# DisplayAddOn_V03-002.net
KiCad netlist of a schematic drawn in EAGLE
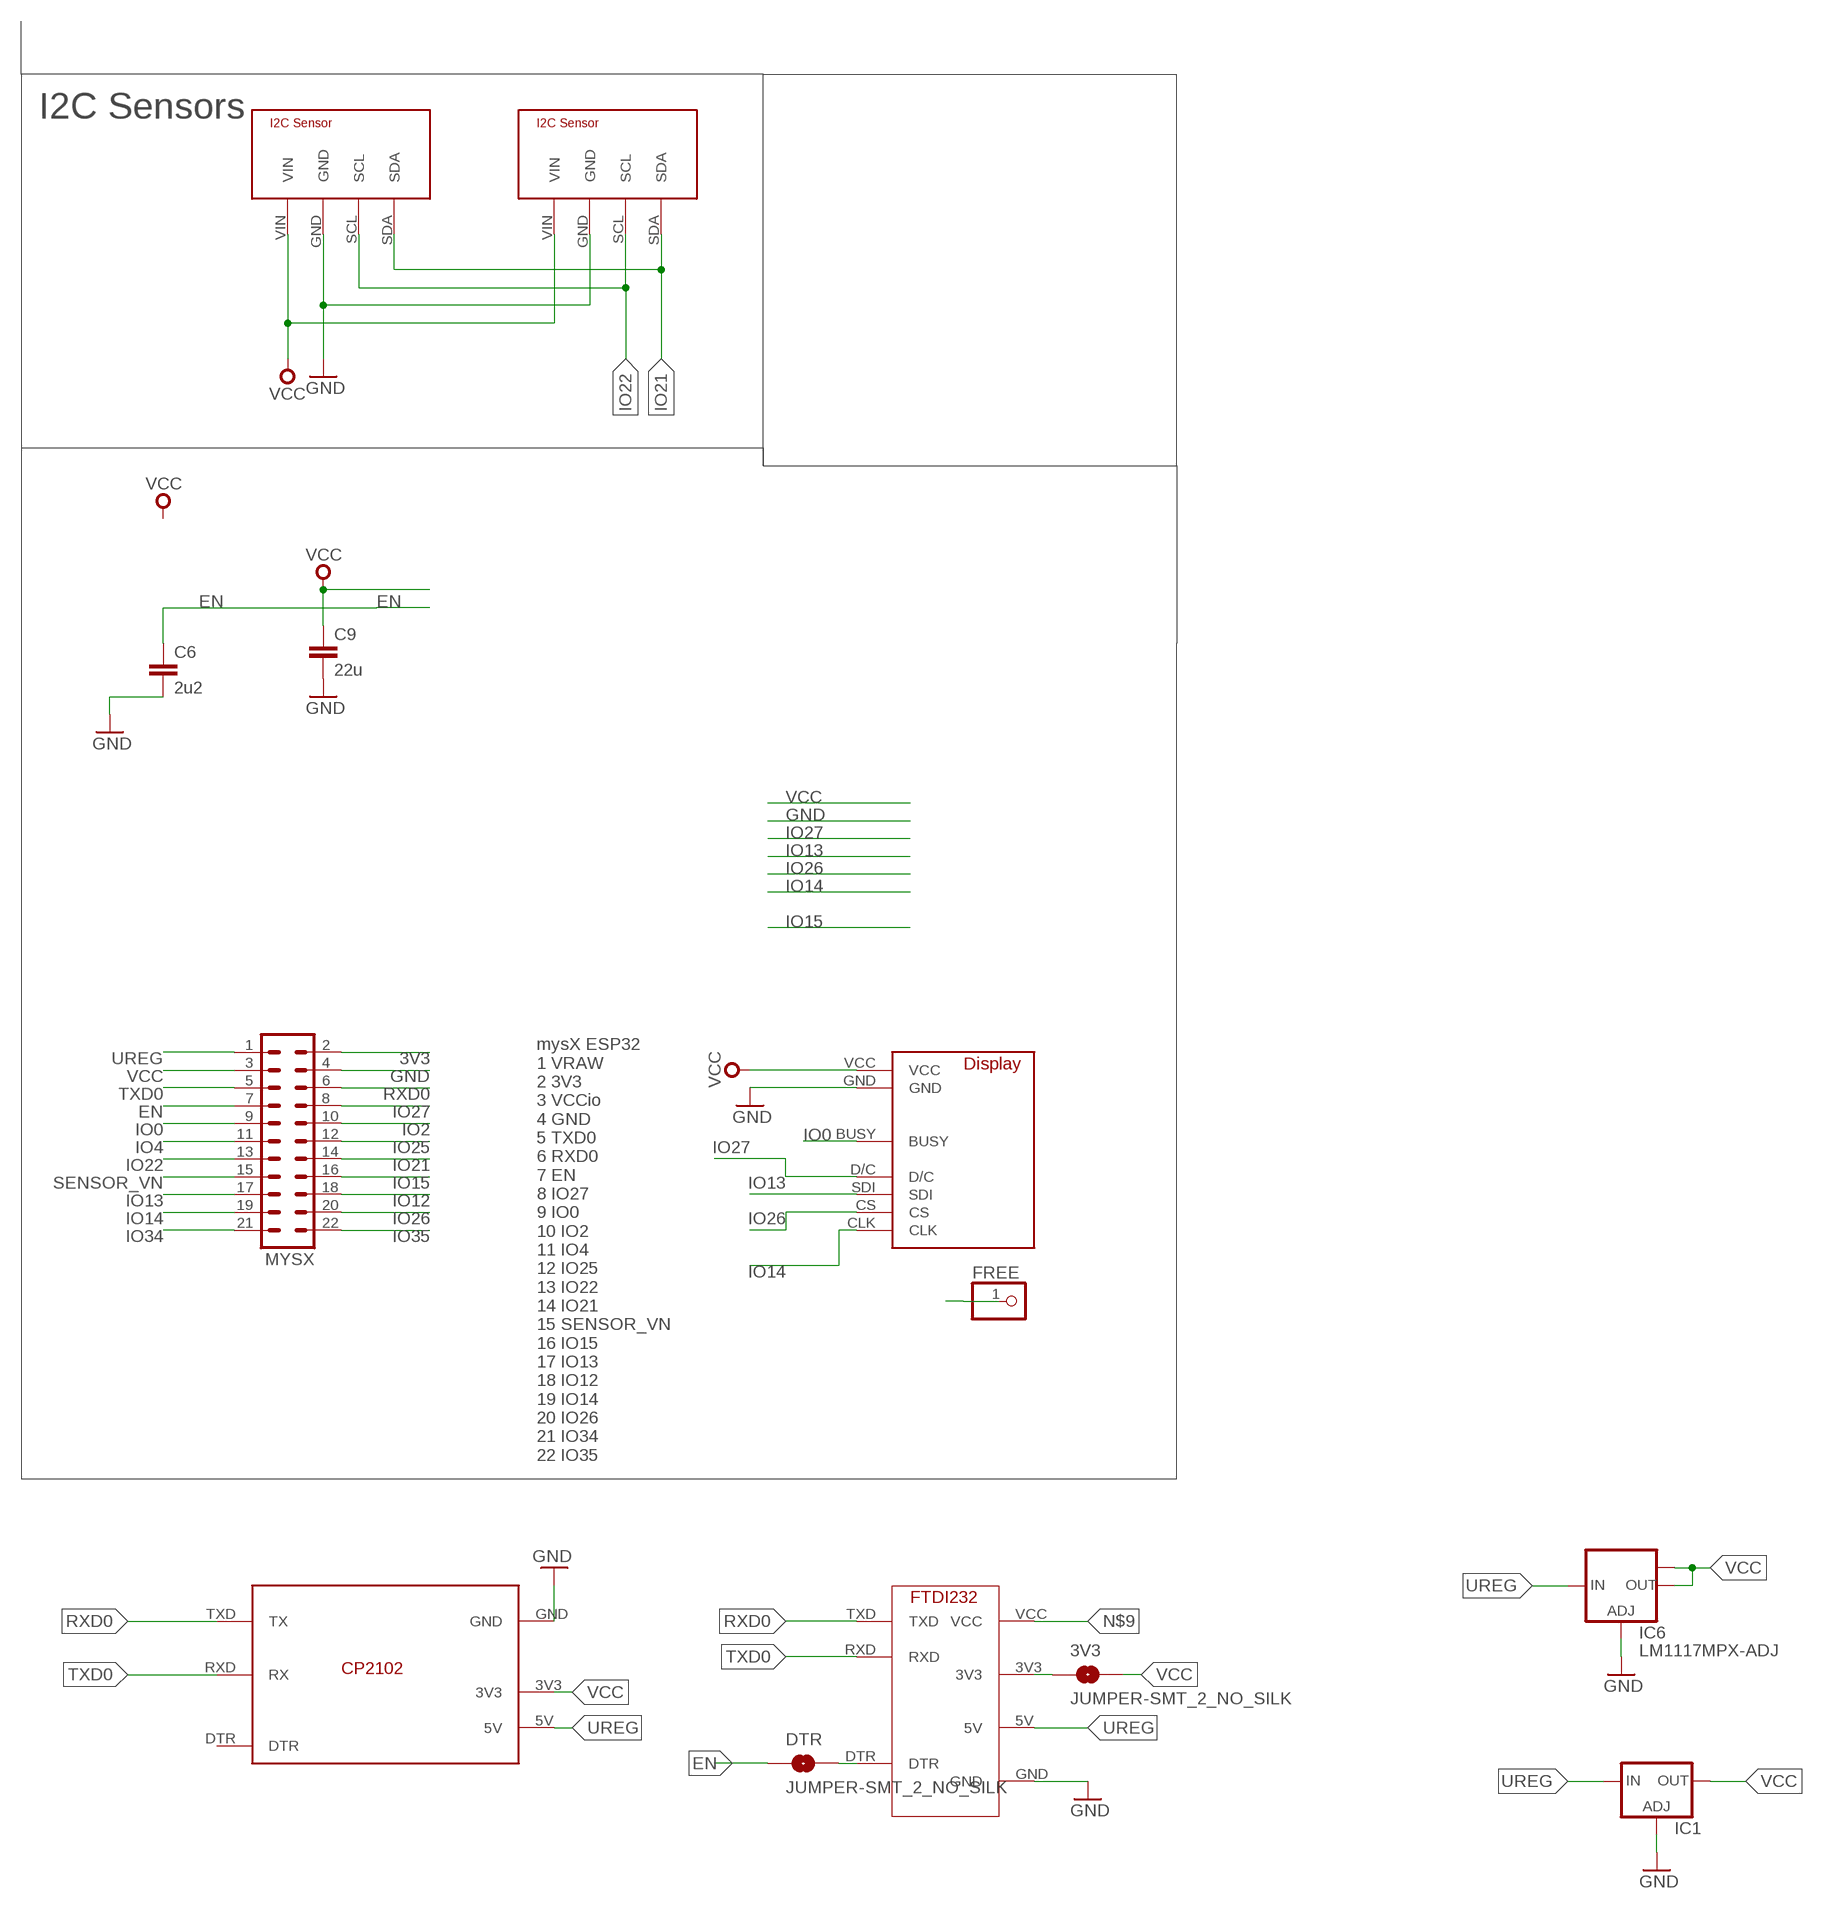
[diagram p0: schematic, sheet 1]

(export (version "E")
  (design (tool "Eeschema 10.0.6"))
  (components
    (comp (ref "3V3")
      (value "JUMPER-SMT_2_NO_SILK")
      (footprint "eagle-import:SMT-JUMPER_2_NO_SILK")
      (libsource (lib "eagle-import") (part "JUMPER-SMT_2_NO_SILK"))
    )
    (comp (ref "C6")
      (value "2u2")
      (footprint "eagle-import:C0805")
      (libsource (lib "eagle-import") (part "C-EUC0805"))
    )
    (comp (ref "C9")
      (value "22u")
      (footprint "eagle-import:C0805")
      (libsource (lib "eagle-import") (part "C-EUC0805"))
    )
    (comp (ref "DTR")
      (value "JUMPER-SMT_2_NO_SILK")
      (footprint "eagle-import:SMT-JUMPER_2_NO_SILK")
      (libsource (lib "eagle-import") (part "JUMPER-SMT_2_NO_SILK"))
    )
    (comp (ref "FREE")
      (value "PINHD-1X1")
      (footprint "eagle-import:1X01")
      (libsource (lib "eagle-import") (part "PINHD-1X1"))
    )
    (comp (ref "HELTEK")
      (value "ZUCZUG_1.54")
      (footprint "eagle-import:ZUCZUG_1.54INCH")
      (libsource (lib "eagle-import") (part "ZUCZUG_1.54"))
    )
    (comp (ref "IC1")
      (value "LD117ADT50TR")
      (footprint "eagle-import:DPACK")
      (libsource (lib "eagle-import") (part "LD117A?DT50TR"))
    )
    (comp (ref "IC6")
      (value "LM1117MPX-ADJ")
      (footprint "eagle-import:SOT223")
      (libsource (lib "eagle-import") (part "LM1117MPX-ADJ"))
    )
    (comp (ref "MYSX")
      (value "MA11-2")
      (footprint "eagle-import:MA11-2")
      (libsource (lib "eagle-import") (part "MA11-2"))
    )
    (comp (ref "U$1")
      (value "CP2101")
      (footprint "eagle-import:CP2101-BEAKOUT")
      (libsource (lib "eagle-import") (part "CP2101"))
    )
    (comp (ref "U$2")
      (value "I2C-BREAKOUT")
      (footprint "eagle-import:I2C_BREAKOUT")
      (libsource (lib "eagle-import") (part "I2C-BREAKOUT"))
    )
    (comp (ref "U$3")
      (value "FTDI232")
      (footprint "eagle-import:FTDI232-LARGE-LESS-PINS")
      (libsource (lib "eagle-import") (part "FTDI232"))
    )
    (comp (ref "U$4")
      (value "I2C-BREAKOUT")
      (footprint "eagle-import:I2C_BREAKOUT")
      (libsource (lib "eagle-import") (part "I2C-BREAKOUT"))
    )
  )
  (nets
    (net (code "1") (name "/3V3") (class "Default")
      (node (ref "MYSX") (pin "2") (pinfunction "2_2") (pintype "passive"))
    )
    (net (code "2") (name "/IO0") (class "Default")
      (node (ref "HELTEK") (pin "BUSY") (pinfunction "BUSY_BUSY") (pintype "bidirectional"))
      (node (ref "MYSX") (pin "9") (pinfunction "9_9") (pintype "passive"))
    )
    (net (code "3") (name "/IO2") (class "Default")
      (node (ref "MYSX") (pin "10") (pinfunction "10_10") (pintype "passive"))
    )
    (net (code "4") (name "/IO4") (class "Default")
      (node (ref "MYSX") (pin "11") (pinfunction "11_11") (pintype "passive"))
    )
    (net (code "5") (name "/IO12") (class "Default")
      (node (ref "MYSX") (pin "18") (pinfunction "18_18") (pintype "passive"))
    )
    (net (code "6") (name "/IO13") (class "Default")
      (node (ref "HELTEK") (pin "SDI") (pinfunction "SDI_SDI") (pintype "bidirectional"))
      (node (ref "MYSX") (pin "17") (pinfunction "17_17") (pintype "passive"))
    )
    (net (code "7") (name "/IO14") (class "Default")
      (node (ref "HELTEK") (pin "CLK") (pinfunction "CLK_CLK") (pintype "bidirectional"))
      (node (ref "MYSX") (pin "19") (pinfunction "19_19") (pintype "passive"))
    )
    (net (code "8") (name "/IO15") (class "Default")
      (node (ref "MYSX") (pin "16") (pinfunction "16_16") (pintype "passive"))
    )
    (net (code "9") (name "/IO25") (class "Default")
      (node (ref "MYSX") (pin "12") (pinfunction "12_12") (pintype "passive"))
    )
    (net (code "10") (name "/IO26") (class "Default")
      (node (ref "HELTEK") (pin "CS") (pinfunction "CS_CS") (pintype "bidirectional"))
      (node (ref "MYSX") (pin "20") (pinfunction "20_20") (pintype "passive"))
    )
    (net (code "11") (name "/IO27") (class "Default")
      (node (ref "HELTEK") (pin "D/C") (pinfunction "D/C_D/C") (pintype "bidirectional"))
      (node (ref "MYSX") (pin "8") (pinfunction "8_8") (pintype "passive"))
    )
    (net (code "12") (name "/IO34") (class "Default")
      (node (ref "MYSX") (pin "21") (pinfunction "21_21") (pintype "passive"))
    )
    (net (code "13") (name "/IO35") (class "Default")
      (node (ref "MYSX") (pin "22") (pinfunction "22_22") (pintype "passive"))
    )
    (net (code "14") (name "/SENSOR_VN") (class "Default")
      (node (ref "MYSX") (pin "15") (pinfunction "15_15") (pintype "passive"))
    )
    (net (code "15") (name "EN") (class "Default")
      (node (ref "C6") (pin "1") (pinfunction "1_1") (pintype "passive"))
      (node (ref "DTR") (pin "1") (pinfunction "1_1") (pintype "passive"))
      (node (ref "MYSX") (pin "7") (pinfunction "7_7") (pintype "passive"))
    )
    (net (code "16") (name "GND") (class "Default")
      (node (ref "C6") (pin "2") (pinfunction "2_2") (pintype "passive"))
      (node (ref "C9") (pin "2") (pinfunction "2_2") (pintype "passive"))
      (node (ref "HELTEK") (pin "GND") (pinfunction "GND_GND") (pintype "power_in"))
      (node (ref "IC1") (pin "1") (pinfunction "ADJ_1") (pintype "input"))
      (node (ref "IC6") (pin "1") (pinfunction "ADJ_1") (pintype "input"))
      (node (ref "MYSX") (pin "4") (pinfunction "4_4") (pintype "passive"))
      (node (ref "U$1") (pin "GND") (pinfunction "GND_GND") (pintype "power_in"))
      (node (ref "U$2") (pin "GND") (pinfunction "GND_GND") (pintype "bidirectional"))
      (node (ref "U$3") (pin "GND") (pinfunction "GND_GND") (pintype "bidirectional"))
      (node (ref "U$4") (pin "GND") (pinfunction "GND_GND") (pintype "bidirectional"))
    )
    (net (code "17") (name "IO21") (class "Default")
      (node (ref "MYSX") (pin "14") (pinfunction "14_14") (pintype "passive"))
      (node (ref "U$2") (pin "SDA") (pinfunction "SDA_SDA") (pintype "bidirectional"))
      (node (ref "U$4") (pin "SDA") (pinfunction "SDA_SDA") (pintype "bidirectional"))
    )
    (net (code "18") (name "IO22") (class "Default")
      (node (ref "MYSX") (pin "13") (pinfunction "13_13") (pintype "passive"))
      (node (ref "U$2") (pin "SCL") (pinfunction "SCL_SCL") (pintype "bidirectional"))
      (node (ref "U$4") (pin "SCL") (pinfunction "SCL_SCL") (pintype "bidirectional"))
    )
    (net (code "19") (name "N$9") (class "Default")
      (node (ref "U$3") (pin "VCC") (pinfunction "VCC_VCC") (pintype "bidirectional"))
    )
    (net (code "20") (name "Net-(3V3-Pad1)") (class "Default")
      (node (ref "3V3") (pin "1") (pinfunction "1_1") (pintype "passive"))
      (node (ref "U$3") (pin "3V3") (pinfunction "3V3_3V3") (pintype "bidirectional"))
    )
    (net (code "21") (name "Net-(DTR-Pad2)") (class "Default")
      (node (ref "DTR") (pin "2") (pinfunction "2_2") (pintype "passive"))
      (node (ref "U$3") (pin "DTR") (pinfunction "DTR_DTR") (pintype "bidirectional"))
    )
    (net (code "22") (name "RXD0") (class "Default")
      (node (ref "MYSX") (pin "6") (pinfunction "6_6") (pintype "passive"))
      (node (ref "U$1") (pin "TXD") (pinfunction "TX_TXD") (pintype "output"))
      (node (ref "U$3") (pin "TXD") (pinfunction "TXD_TXD") (pintype "bidirectional"))
    )
    (net (code "23") (name "TXD0") (class "Default")
      (node (ref "MYSX") (pin "5") (pinfunction "5_5") (pintype "passive"))
      (node (ref "U$1") (pin "RXD") (pinfunction "RX_RXD") (pintype "input"))
      (node (ref "U$3") (pin "RXD") (pinfunction "RXD_RXD") (pintype "bidirectional"))
    )
    (net (code "24") (name "UREG") (class "Default")
      (node (ref "IC1") (pin "3") (pinfunction "IN_3") (pintype "input"))
      (node (ref "IC6") (pin "3") (pinfunction "IN_3") (pintype "input"))
      (node (ref "MYSX") (pin "1") (pinfunction "1_1") (pintype "passive"))
      (node (ref "U$1") (pin "5V") (pinfunction "5V_5V") (pintype "power_in"))
      (node (ref "U$3") (pin "5V") (pinfunction "5V_5V") (pintype "bidirectional"))
    )
    (net (code "25") (name "VCC") (class "Default")
      (node (ref "3V3") (pin "2") (pinfunction "2_2") (pintype "passive"))
      (node (ref "C9") (pin "1") (pinfunction "1_1") (pintype "passive"))
      (node (ref "HELTEK") (pin "VCC") (pinfunction "VCC_VCC") (pintype "power_in"))
      (node (ref "IC1") (pin "4") (pinfunction "OUT_4") (pintype "passive"))
      (node (ref "IC6") (pin "2") (pinfunction "OUT_2") (pintype "passive"))
      (node (ref "IC6") (pin "TAB") (pinfunction "OUT1_TAB") (pintype "passive"))
      (node (ref "MYSX") (pin "3") (pinfunction "3_3") (pintype "passive"))
      (node (ref "U$1") (pin "3V3") (pinfunction "3V3_3V3") (pintype "power_in"))
      (node (ref "U$2") (pin "VIN") (pinfunction "VIN_VIN") (pintype "bidirectional"))
      (node (ref "U$4") (pin "VIN") (pinfunction "VIN_VIN") (pintype "bidirectional"))
    )
    (net (code "26") (name "unconnected-(FREE-Pad1)") (class "Default")
      (node (ref "FREE") (pin "1") (pinfunction "1_1") (pintype "passive"))
    )
    (net (code "27") (name "unconnected-(U$1-PadDTR)") (class "Default")
      (node (ref "U$1") (pin "DTR") (pinfunction "DTR_DTR") (pintype "bidirectional"))
    )
  )
)
